# DIGITAL_INPUTS.net
KiCad netlist of a schematic drawn in Altium Designer
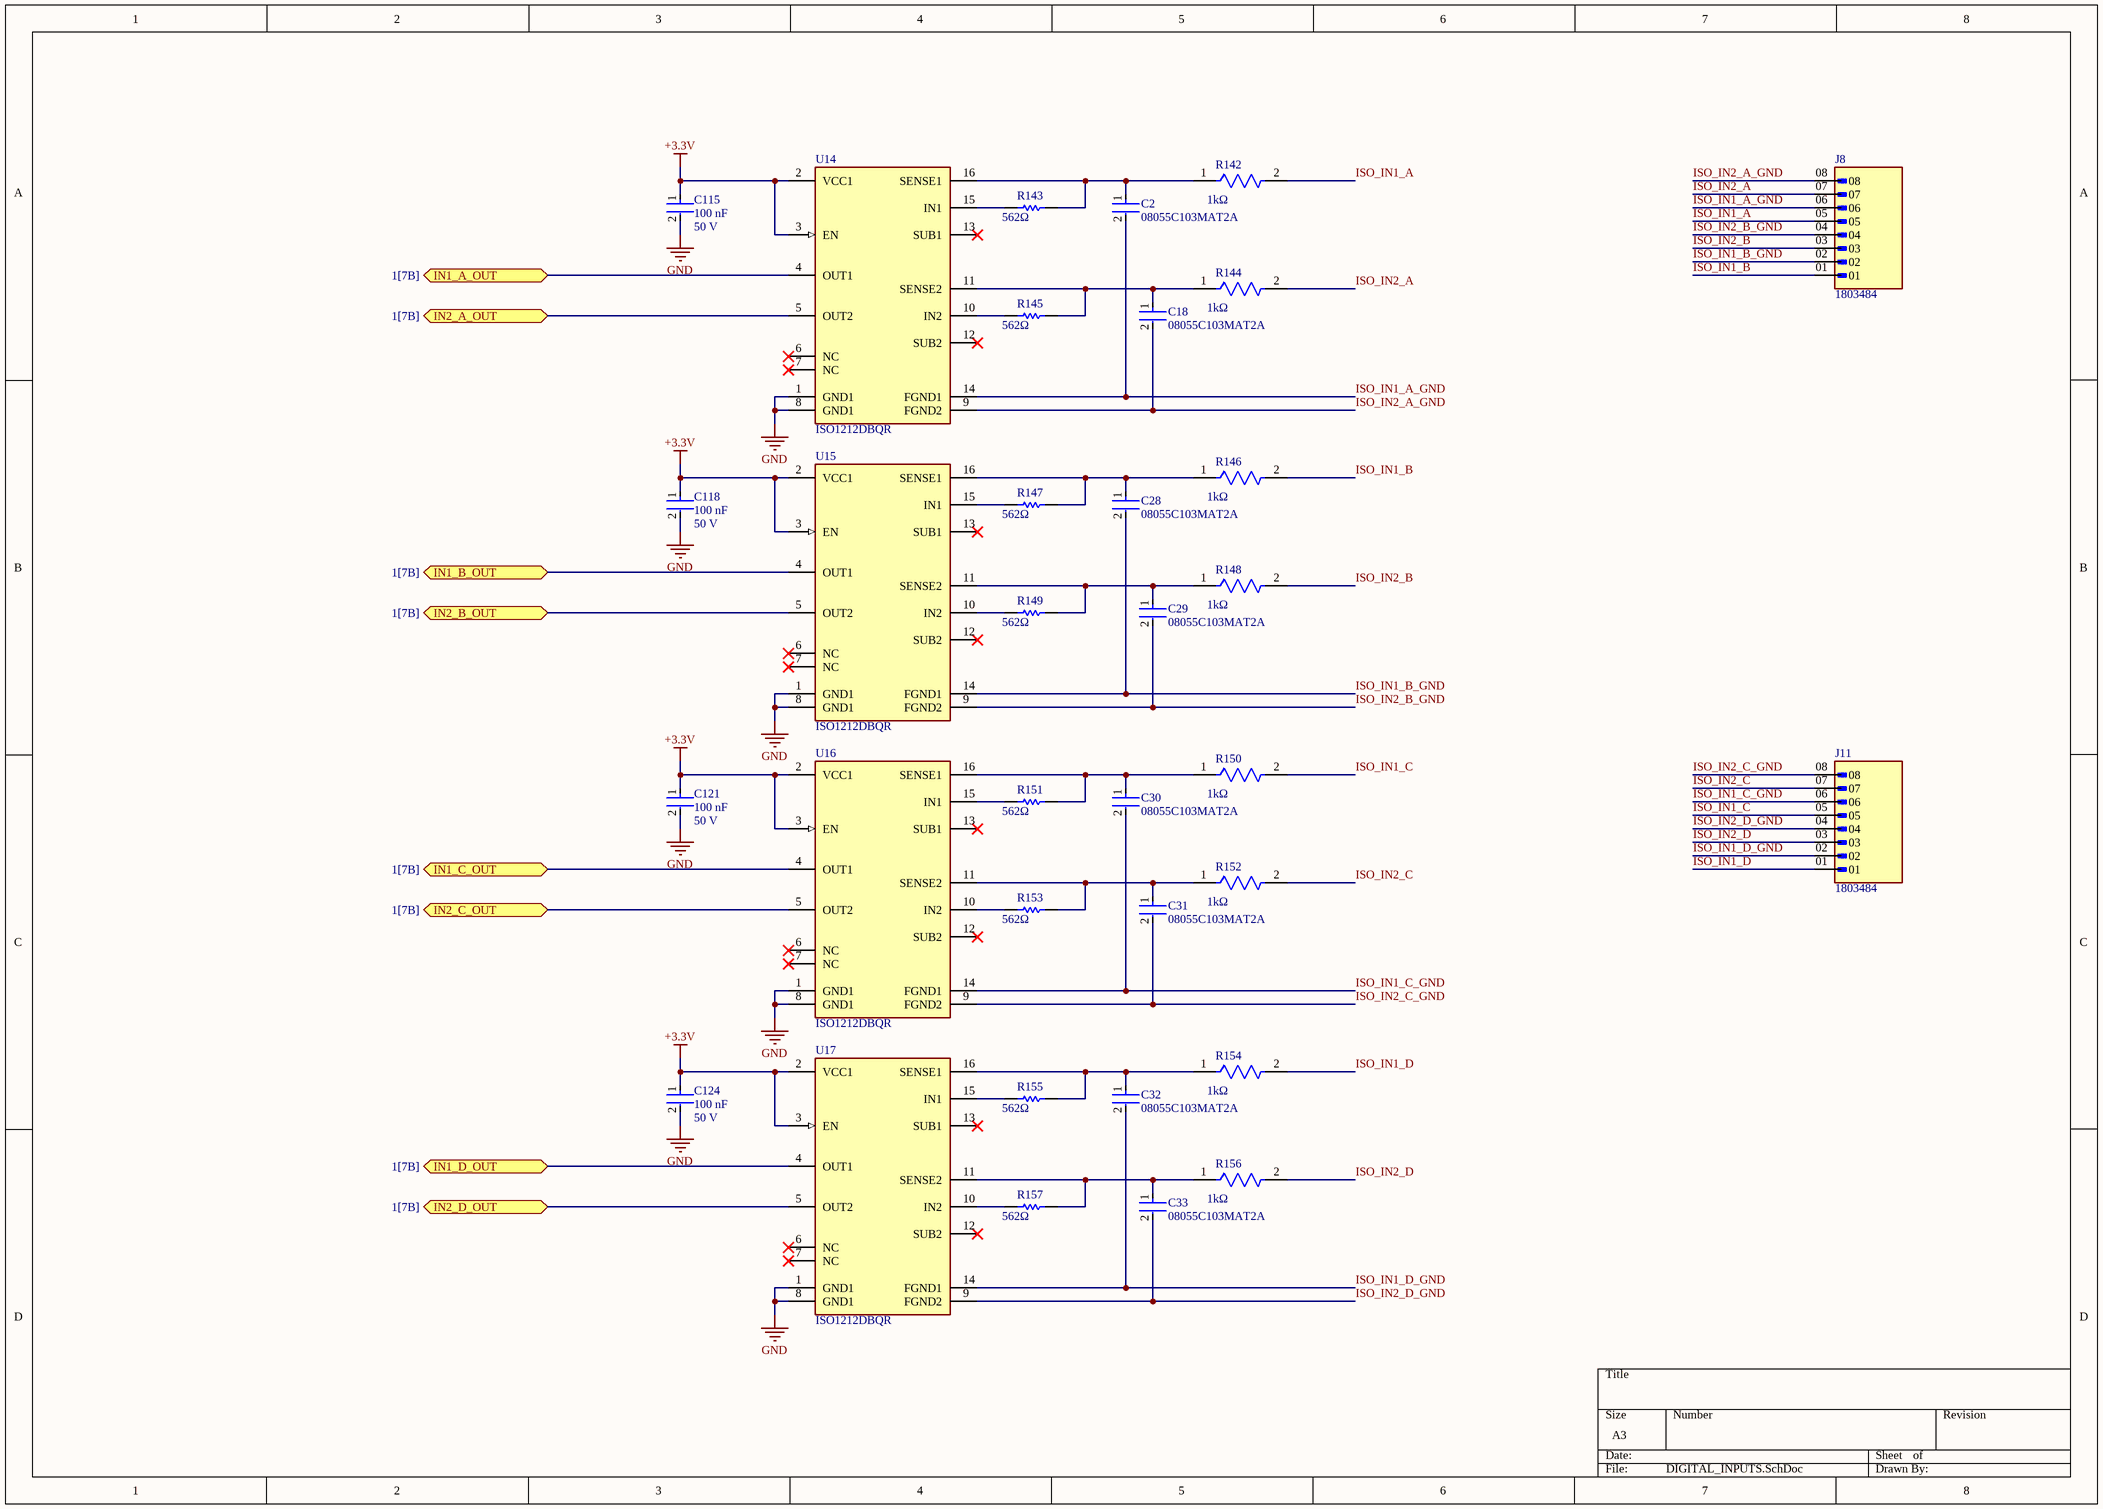
[diagram p0: DIGITAL_INPUTS.SchDoc]

(export (version "E")
  (design (tool "Eeschema 10.0.6"))
  (components
    (comp (ref "C2")
      (value "08055C103MAT2A")
      (footprint "FP-0805-L_2_01_0_2-W_1_25-MFG")
      (description "General Purpose Ceramic Capacitor, 0805, 10nF, 20%, X7R, 0.15, 50V")
      (fields (field (name "VOLTAGE") "50V") (field (name "TOLERANCE") "20%"))
      (libsource (lib "Altium Content Vault") (part "02cd4be3c70576c341d710602a673aa"))
    )
    (comp (ref "C18")
      (value "08055C103MAT2A")
      (footprint "FP-0805-L_2_01_0_2-W_1_25-MFG")
      (description "General Purpose Ceramic Capacitor, 0805, 10nF, 20%, X7R, 0.15, 50V")
      (fields (field (name "VOLTAGE") "50V") (field (name "TOLERANCE") "20%"))
      (libsource (lib "Altium Content Vault") (part "02cd4be3c70576c341d710602a673aa"))
    )
    (comp (ref "C28")
      (value "08055C103MAT2A")
      (footprint "FP-0805-L_2_01_0_2-W_1_25-MFG")
      (description "General Purpose Ceramic Capacitor, 0805, 10nF, 20%, X7R, 0.15, 50V")
      (fields (field (name "VOLTAGE") "50V") (field (name "TOLERANCE") "20%"))
      (libsource (lib "Altium Content Vault") (part "02cd4be3c70576c341d710602a673aa"))
    )
    (comp (ref "C29")
      (value "08055C103MAT2A")
      (footprint "FP-0805-L_2_01_0_2-W_1_25-MFG")
      (description "General Purpose Ceramic Capacitor, 0805, 10nF, 20%, X7R, 0.15, 50V")
      (fields (field (name "VOLTAGE") "50V") (field (name "TOLERANCE") "20%"))
      (libsource (lib "Altium Content Vault") (part "02cd4be3c70576c341d710602a673aa"))
    )
    (comp (ref "C30")
      (value "08055C103MAT2A")
      (footprint "FP-0805-L_2_01_0_2-W_1_25-MFG")
      (description "General Purpose Ceramic Capacitor, 0805, 10nF, 20%, X7R, 0.15, 50V")
      (fields (field (name "VOLTAGE") "50V") (field (name "TOLERANCE") "20%"))
      (libsource (lib "Altium Content Vault") (part "02cd4be3c70576c341d710602a673aa"))
    )
    (comp (ref "C31")
      (value "08055C103MAT2A")
      (footprint "FP-0805-L_2_01_0_2-W_1_25-MFG")
      (description "General Purpose Ceramic Capacitor, 0805, 10nF, 20%, X7R, 0.15, 50V")
      (fields (field (name "VOLTAGE") "50V") (field (name "TOLERANCE") "20%"))
      (libsource (lib "Altium Content Vault") (part "02cd4be3c70576c341d710602a673aa"))
    )
    (comp (ref "C32")
      (value "08055C103MAT2A")
      (footprint "FP-0805-L_2_01_0_2-W_1_25-MFG")
      (description "General Purpose Ceramic Capacitor, 0805, 10nF, 20%, X7R, 0.15, 50V")
      (fields (field (name "VOLTAGE") "50V") (field (name "TOLERANCE") "20%"))
      (libsource (lib "Altium Content Vault") (part "02cd4be3c70576c341d710602a673aa"))
    )
    (comp (ref "C33")
      (value "08055C103MAT2A")
      (footprint "FP-0805-L_2_01_0_2-W_1_25-MFG")
      (description "General Purpose Ceramic Capacitor, 0805, 10nF, 20%, X7R, 0.15, 50V")
      (fields (field (name "VOLTAGE") "50V") (field (name "TOLERANCE") "20%"))
      (libsource (lib "Altium Content Vault") (part "02cd4be3c70576c341d710602a673aa"))
    )
    (comp (ref "C115")
      (value "100 nF")
      (footprint "FP-C0603C-CF-IPC_B")
      (description "CAP CER 0.1UF 50V 20% X7R 0603")
      (fields
        (field (name "VOLTAGE RATING") "50 V")
        (field (name "MANUFACTURER PART NUMBER") "C0603C104M5RACTU")
        (field (name "MANUFACTURER") "KEMET")
      )
      (libsource (lib "Altium Content Vault") (part "b4654b650e69147ec39a6b967a45e02"))
    )
    (comp (ref "C118")
      (value "100 nF")
      (footprint "FP-C0603C-CF-IPC_B")
      (description "CAP CER 0.1UF 50V 20% X7R 0603")
      (fields
        (field (name "VOLTAGE RATING") "50 V")
        (field (name "MANUFACTURER PART NUMBER") "C0603C104M5RACTU")
        (field (name "MANUFACTURER") "KEMET")
      )
      (libsource (lib "Altium Content Vault") (part "b4654b650e69147ec39a6b967a45e02"))
    )
    (comp (ref "C121")
      (value "100 nF")
      (footprint "FP-C0603C-CF-IPC_B")
      (description "CAP CER 0.1UF 50V 20% X7R 0603")
      (fields
        (field (name "VOLTAGE RATING") "50 V")
        (field (name "MANUFACTURER PART NUMBER") "C0603C104M5RACTU")
        (field (name "MANUFACTURER") "KEMET")
      )
      (libsource (lib "Altium Content Vault") (part "b4654b650e69147ec39a6b967a45e02"))
    )
    (comp (ref "C124")
      (value "100 nF")
      (footprint "FP-C0603C-CF-IPC_B")
      (description "CAP CER 0.1UF 50V 20% X7R 0603")
      (fields
        (field (name "VOLTAGE RATING") "50 V")
        (field (name "MANUFACTURER PART NUMBER") "C0603C104M5RACTU")
        (field (name "MANUFACTURER") "KEMET")
      )
      (libsource (lib "Altium Content Vault") (part "b4654b650e69147ec39a6b967a45e02"))
    )
    (comp (ref "J8")
      (value "1803484")
      (footprint "1803484:PHOENIX_1803484")
      (fields (field (name "MF") "{'manufacturer': u'Phoenix Contact'}"))
      (libsource (lib "*") (part "1803484"))
    )
    (comp (ref "J11")
      (value "1803484")
      (footprint "1803484:PHOENIX_1803484")
      (fields (field (name "MF") "{'manufacturer': u'Phoenix Contact'}"))
      (libsource (lib "*") (part "1803484"))
    )
    (comp (ref "R142")
      (value "AC0603FR-071KL")
      (footprint "FP-AC0603-IPC_B")
      (description "RES 1kΩ 1.00% 0.1W 0603")
      (fields (field (name "TOLERANCE") "1%") (field (name "RESISTANCE") "1kΩ"))
      (libsource (lib "Altium Content Vault") (part "1029c3af85768c4190bb7ad29bc67b5"))
    )
    (comp (ref "R143")
      (value "RC0603FR-07562RL")
      (footprint "RESC1608X55X25ML10T15")
      (fields (field (name "MANUFACTURER") "Yageo") (field (name "RESISTANCE") "562Ω"))
      (libsource (lib "Altium Content Vault") (part "RES"))
    )
    (comp (ref "R144")
      (value "AC0603FR-071KL")
      (footprint "FP-AC0603-IPC_B")
      (description "RES 1kΩ 1.00% 0.1W 0603")
      (fields (field (name "TOLERANCE") "1%") (field (name "RESISTANCE") "1kΩ"))
      (libsource (lib "Altium Content Vault") (part "1029c3af85768c4190bb7ad29bc67b5"))
    )
    (comp (ref "R145")
      (value "RC0603FR-07562RL")
      (footprint "RESC1608X55X25ML10T15")
      (fields (field (name "MANUFACTURER") "Yageo") (field (name "RESISTANCE") "562Ω"))
      (libsource (lib "Altium Content Vault") (part "RES"))
    )
    (comp (ref "R146")
      (value "AC0603FR-071KL")
      (footprint "FP-AC0603-IPC_B")
      (description "RES 1kΩ 1.00% 0.1W 0603")
      (fields (field (name "TOLERANCE") "1%") (field (name "RESISTANCE") "1kΩ"))
      (libsource (lib "Altium Content Vault") (part "1029c3af85768c4190bb7ad29bc67b5"))
    )
    (comp (ref "R147")
      (value "RC0603FR-07562RL")
      (footprint "RESC1608X55X25ML10T15")
      (fields (field (name "MANUFACTURER") "Yageo") (field (name "RESISTANCE") "562Ω"))
      (libsource (lib "Altium Content Vault") (part "RES"))
    )
    (comp (ref "R148")
      (value "AC0603FR-071KL")
      (footprint "FP-AC0603-IPC_B")
      (description "RES 1kΩ 1.00% 0.1W 0603")
      (fields (field (name "TOLERANCE") "1%") (field (name "RESISTANCE") "1kΩ"))
      (libsource (lib "Altium Content Vault") (part "1029c3af85768c4190bb7ad29bc67b5"))
    )
    (comp (ref "R149")
      (value "RC0603FR-07562RL")
      (footprint "RESC1608X55X25ML10T15")
      (fields (field (name "MANUFACTURER") "Yageo") (field (name "RESISTANCE") "562Ω"))
      (libsource (lib "Altium Content Vault") (part "RES"))
    )
    (comp (ref "R150")
      (value "AC0603FR-071KL")
      (footprint "FP-AC0603-IPC_B")
      (description "RES 1kΩ 1.00% 0.1W 0603")
      (fields (field (name "TOLERANCE") "1%") (field (name "RESISTANCE") "1kΩ"))
      (libsource (lib "Altium Content Vault") (part "1029c3af85768c4190bb7ad29bc67b5"))
    )
    (comp (ref "R151")
      (value "RC0603FR-07562RL")
      (footprint "RESC1608X55X25ML10T15")
      (fields (field (name "MANUFACTURER") "Yageo") (field (name "RESISTANCE") "562Ω"))
      (libsource (lib "Altium Content Vault") (part "RES"))
    )
    (comp (ref "R152")
      (value "AC0603FR-071KL")
      (footprint "FP-AC0603-IPC_B")
      (description "RES 1kΩ 1.00% 0.1W 0603")
      (fields (field (name "TOLERANCE") "1%") (field (name "RESISTANCE") "1kΩ"))
      (libsource (lib "Altium Content Vault") (part "1029c3af85768c4190bb7ad29bc67b5"))
    )
    (comp (ref "R153")
      (value "RC0603FR-07562RL")
      (footprint "RESC1608X55X25ML10T15")
      (fields (field (name "MANUFACTURER") "Yageo") (field (name "RESISTANCE") "562Ω"))
      (libsource (lib "Altium Content Vault") (part "RES"))
    )
    (comp (ref "R154")
      (value "AC0603FR-071KL")
      (footprint "FP-AC0603-IPC_B")
      (description "RES 1kΩ 1.00% 0.1W 0603")
      (fields (field (name "TOLERANCE") "1%") (field (name "RESISTANCE") "1kΩ"))
      (libsource (lib "Altium Content Vault") (part "1029c3af85768c4190bb7ad29bc67b5"))
    )
    (comp (ref "R155")
      (value "RC0603FR-07562RL")
      (footprint "RESC1608X55X25ML10T15")
      (fields (field (name "MANUFACTURER") "Yageo") (field (name "RESISTANCE") "562Ω"))
      (libsource (lib "Altium Content Vault") (part "RES"))
    )
    (comp (ref "R156")
      (value "AC0603FR-071KL")
      (footprint "FP-AC0603-IPC_B")
      (description "RES 1kΩ 1.00% 0.1W 0603")
      (fields (field (name "TOLERANCE") "1%") (field (name "RESISTANCE") "1kΩ"))
      (libsource (lib "Altium Content Vault") (part "1029c3af85768c4190bb7ad29bc67b5"))
    )
    (comp (ref "R157")
      (value "RC0603FR-07562RL")
      (footprint "RESC1608X55X25ML10T15")
      (fields (field (name "MANUFACTURER") "Yageo") (field (name "RESISTANCE") "562Ω"))
      (libsource (lib "Altium Content Vault") (part "RES"))
    )
    (comp (ref "U14")
      (value "ISO1212DBQR")
      (footprint "FP-DBQ0016A-MFG")
      (description "ISOLATED 24-V TO 60-V DIGITAL IN")
      (fields
        (field (name "OCTOPART") "https://octopart.com/iso1212dbqr-texas+instruments-84619664")
        (field (name "MANUFACTURER") "Texas Instruments")
      )
      (libsource (lib "Altium Content Vault") (part "047d738653624c8e0ece078ac6d36bd"))
    )
    (comp (ref "U15")
      (value "ISO1212DBQR")
      (footprint "FP-DBQ0016A-MFG")
      (description "ISOLATED 24-V TO 60-V DIGITAL IN")
      (fields
        (field (name "OCTOPART") "https://octopart.com/iso1212dbqr-texas+instruments-84619664")
        (field (name "MANUFACTURER") "Texas Instruments")
      )
      (libsource (lib "Altium Content Vault") (part "047d738653624c8e0ece078ac6d36bd"))
    )
    (comp (ref "U16")
      (value "ISO1212DBQR")
      (footprint "FP-DBQ0016A-MFG")
      (description "ISOLATED 24-V TO 60-V DIGITAL IN")
      (fields
        (field (name "OCTOPART") "https://octopart.com/iso1212dbqr-texas+instruments-84619664")
        (field (name "MANUFACTURER") "Texas Instruments")
      )
      (libsource (lib "Altium Content Vault") (part "047d738653624c8e0ece078ac6d36bd"))
    )
    (comp (ref "U17")
      (value "ISO1212DBQR")
      (footprint "FP-DBQ0016A-MFG")
      (description "ISOLATED 24-V TO 60-V DIGITAL IN")
      (fields
        (field (name "OCTOPART") "https://octopart.com/iso1212dbqr-texas+instruments-84619664")
        (field (name "MANUFACTURER") "Texas Instruments")
      )
      (libsource (lib "Altium Content Vault") (part "047d738653624c8e0ece078ac6d36bd"))
    )
  )
  (nets
    (net (code "1") (name "+3.3V") (class "Default")
      (node (ref "C115") (pin "1") (pinfunction "1_1") (pintype "passive"))
      (node (ref "C118") (pin "1") (pinfunction "1_1") (pintype "passive"))
      (node (ref "C121") (pin "1") (pinfunction "1_1") (pintype "passive"))
      (node (ref "C124") (pin "1") (pinfunction "1_1") (pintype "passive"))
      (node (ref "U14") (pin "2") (pinfunction "VCC1_2") (pintype "power_in"))
      (node (ref "U14") (pin "3") (pinfunction "EN_3") (pintype "input"))
      (node (ref "U15") (pin "2") (pinfunction "VCC1_2") (pintype "power_in"))
      (node (ref "U15") (pin "3") (pinfunction "EN_3") (pintype "input"))
      (node (ref "U16") (pin "2") (pinfunction "VCC1_2") (pintype "power_in"))
      (node (ref "U16") (pin "3") (pinfunction "EN_3") (pintype "input"))
      (node (ref "U17") (pin "2") (pinfunction "VCC1_2") (pintype "power_in"))
      (node (ref "U17") (pin "3") (pinfunction "EN_3") (pintype "input"))
    )
    (net (code "2") (name "/IN1_A_OUT") (class "Default")
      (node (ref "U14") (pin "4") (pinfunction "OUT1_4") (pintype "passive"))
    )
    (net (code "3") (name "/IN1_B_OUT") (class "Default")
      (node (ref "U15") (pin "4") (pinfunction "OUT1_4") (pintype "passive"))
    )
    (net (code "4") (name "/IN1_C_OUT") (class "Default")
      (node (ref "U16") (pin "4") (pinfunction "OUT1_4") (pintype "passive"))
    )
    (net (code "5") (name "/IN1_D_OUT") (class "Default")
      (node (ref "U17") (pin "4") (pinfunction "OUT1_4") (pintype "passive"))
    )
    (net (code "6") (name "/IN2_A_OUT") (class "Default")
      (node (ref "U14") (pin "5") (pinfunction "OUT2_5") (pintype "passive"))
    )
    (net (code "7") (name "/IN2_B_OUT") (class "Default")
      (node (ref "U15") (pin "5") (pinfunction "OUT2_5") (pintype "passive"))
    )
    (net (code "8") (name "/IN2_C_OUT") (class "Default")
      (node (ref "U16") (pin "5") (pinfunction "OUT2_5") (pintype "passive"))
    )
    (net (code "9") (name "/IN2_D_OUT") (class "Default")
      (node (ref "U17") (pin "5") (pinfunction "OUT2_5") (pintype "passive"))
    )
    (net (code "10") (name "/ISO_IN1_A") (class "Default")
      (node (ref "J8") (pin "05") (pinfunction "05_05") (pintype "passive"))
      (node (ref "R142") (pin "2") (pinfunction "2_2") (pintype "passive"))
    )
    (net (code "11") (name "/ISO_IN1_A_GND") (class "Default")
      (node (ref "C2") (pin "2") (pinfunction "2_2") (pintype "passive"))
      (node (ref "J8") (pin "06") (pinfunction "06_06") (pintype "passive"))
      (node (ref "U14") (pin "14") (pinfunction "FGND1_14") (pintype "power_in"))
    )
    (net (code "12") (name "/ISO_IN1_B") (class "Default")
      (node (ref "J8") (pin "01") (pinfunction "01_01") (pintype "passive"))
      (node (ref "R146") (pin "2") (pinfunction "2_2") (pintype "passive"))
    )
    (net (code "13") (name "/ISO_IN1_B_GND") (class "Default")
      (node (ref "C28") (pin "2") (pinfunction "2_2") (pintype "passive"))
      (node (ref "J8") (pin "02") (pinfunction "02_02") (pintype "passive"))
      (node (ref "U15") (pin "14") (pinfunction "FGND1_14") (pintype "power_in"))
    )
    (net (code "14") (name "/ISO_IN1_C") (class "Default")
      (node (ref "J11") (pin "05") (pinfunction "05_05") (pintype "passive"))
      (node (ref "R150") (pin "2") (pinfunction "2_2") (pintype "passive"))
    )
    (net (code "15") (name "/ISO_IN1_C_GND") (class "Default")
      (node (ref "C30") (pin "2") (pinfunction "2_2") (pintype "passive"))
      (node (ref "J11") (pin "06") (pinfunction "06_06") (pintype "passive"))
      (node (ref "U16") (pin "14") (pinfunction "FGND1_14") (pintype "power_in"))
    )
    (net (code "16") (name "/ISO_IN1_D") (class "Default")
      (node (ref "J11") (pin "01") (pinfunction "01_01") (pintype "passive"))
      (node (ref "R154") (pin "2") (pinfunction "2_2") (pintype "passive"))
    )
    (net (code "17") (name "/ISO_IN1_D_GND") (class "Default")
      (node (ref "C32") (pin "2") (pinfunction "2_2") (pintype "passive"))
      (node (ref "J11") (pin "02") (pinfunction "02_02") (pintype "passive"))
      (node (ref "U17") (pin "14") (pinfunction "FGND1_14") (pintype "power_in"))
    )
    (net (code "18") (name "/ISO_IN2_A") (class "Default")
      (node (ref "J8") (pin "07") (pinfunction "07_07") (pintype "passive"))
      (node (ref "R144") (pin "2") (pinfunction "2_2") (pintype "passive"))
    )
    (net (code "19") (name "/ISO_IN2_A_GND") (class "Default")
      (node (ref "C18") (pin "2") (pinfunction "2_2") (pintype "passive"))
      (node (ref "J8") (pin "08") (pinfunction "08_08") (pintype "passive"))
      (node (ref "U14") (pin "9") (pinfunction "FGND2_9") (pintype "power_in"))
    )
    (net (code "20") (name "/ISO_IN2_B") (class "Default")
      (node (ref "J8") (pin "03") (pinfunction "03_03") (pintype "passive"))
      (node (ref "R148") (pin "2") (pinfunction "2_2") (pintype "passive"))
    )
    (net (code "21") (name "/ISO_IN2_B_GND") (class "Default")
      (node (ref "C29") (pin "2") (pinfunction "2_2") (pintype "passive"))
      (node (ref "J8") (pin "04") (pinfunction "04_04") (pintype "passive"))
      (node (ref "U15") (pin "9") (pinfunction "FGND2_9") (pintype "power_in"))
    )
    (net (code "22") (name "/ISO_IN2_C") (class "Default")
      (node (ref "J11") (pin "07") (pinfunction "07_07") (pintype "passive"))
      (node (ref "R152") (pin "2") (pinfunction "2_2") (pintype "passive"))
    )
    (net (code "23") (name "/ISO_IN2_C_GND") (class "Default")
      (node (ref "C31") (pin "2") (pinfunction "2_2") (pintype "passive"))
      (node (ref "J11") (pin "08") (pinfunction "08_08") (pintype "passive"))
      (node (ref "U16") (pin "9") (pinfunction "FGND2_9") (pintype "power_in"))
    )
    (net (code "24") (name "/ISO_IN2_D") (class "Default")
      (node (ref "J11") (pin "03") (pinfunction "03_03") (pintype "passive"))
      (node (ref "R156") (pin "2") (pinfunction "2_2") (pintype "passive"))
    )
    (net (code "25") (name "/ISO_IN2_D_GND") (class "Default")
      (node (ref "C33") (pin "2") (pinfunction "2_2") (pintype "passive"))
      (node (ref "J11") (pin "04") (pinfunction "04_04") (pintype "passive"))
      (node (ref "U17") (pin "9") (pinfunction "FGND2_9") (pintype "power_in"))
    )
    (net (code "26") (name "GND") (class "Default")
      (node (ref "C115") (pin "2") (pinfunction "2_2") (pintype "passive"))
      (node (ref "C118") (pin "2") (pinfunction "2_2") (pintype "passive"))
      (node (ref "C121") (pin "2") (pinfunction "2_2") (pintype "passive"))
      (node (ref "C124") (pin "2") (pinfunction "2_2") (pintype "passive"))
      (node (ref "U14") (pin "1") (pinfunction "GND1_1") (pintype "power_in"))
      (node (ref "U14") (pin "8") (pinfunction "GND1_8") (pintype "power_in"))
      (node (ref "U15") (pin "1") (pinfunction "GND1_1") (pintype "power_in"))
      (node (ref "U15") (pin "8") (pinfunction "GND1_8") (pintype "power_in"))
      (node (ref "U16") (pin "1") (pinfunction "GND1_1") (pintype "power_in"))
      (node (ref "U16") (pin "8") (pinfunction "GND1_8") (pintype "power_in"))
      (node (ref "U17") (pin "1") (pinfunction "GND1_1") (pintype "power_in"))
      (node (ref "U17") (pin "8") (pinfunction "GND1_8") (pintype "power_in"))
    )
    (net (code "27") (name "Net-(U14-IN1)") (class "Default")
      (node (ref "R143") (pin "1") (pinfunction "1_1") (pintype "passive"))
      (node (ref "U14") (pin "15") (pinfunction "IN1_15") (pintype "passive"))
    )
    (net (code "28") (name "Net-(U14-IN2)") (class "Default")
      (node (ref "R145") (pin "1") (pinfunction "1_1") (pintype "passive"))
      (node (ref "U14") (pin "10") (pinfunction "IN2_10") (pintype "passive"))
    )
    (net (code "29") (name "Net-(U14-SENSE1)") (class "Default")
      (node (ref "C2") (pin "1") (pinfunction "1_1") (pintype "passive"))
      (node (ref "R142") (pin "1") (pinfunction "1_1") (pintype "passive"))
      (node (ref "R143") (pin "2") (pinfunction "2_2") (pintype "passive"))
      (node (ref "U14") (pin "16") (pinfunction "SENSE1_16") (pintype "passive"))
    )
    (net (code "30") (name "Net-(U14-SENSE2)") (class "Default")
      (node (ref "C18") (pin "1") (pinfunction "1_1") (pintype "passive"))
      (node (ref "R144") (pin "1") (pinfunction "1_1") (pintype "passive"))
      (node (ref "R145") (pin "2") (pinfunction "2_2") (pintype "passive"))
      (node (ref "U14") (pin "11") (pinfunction "SENSE2_11") (pintype "passive"))
    )
    (net (code "31") (name "Net-(U15-IN1)") (class "Default")
      (node (ref "R147") (pin "1") (pinfunction "1_1") (pintype "passive"))
      (node (ref "U15") (pin "15") (pinfunction "IN1_15") (pintype "passive"))
    )
    (net (code "32") (name "Net-(U15-IN2)") (class "Default")
      (node (ref "R149") (pin "1") (pinfunction "1_1") (pintype "passive"))
      (node (ref "U15") (pin "10") (pinfunction "IN2_10") (pintype "passive"))
    )
    (net (code "33") (name "Net-(U15-SENSE1)") (class "Default")
      (node (ref "C28") (pin "1") (pinfunction "1_1") (pintype "passive"))
      (node (ref "R146") (pin "1") (pinfunction "1_1") (pintype "passive"))
      (node (ref "R147") (pin "2") (pinfunction "2_2") (pintype "passive"))
      (node (ref "U15") (pin "16") (pinfunction "SENSE1_16") (pintype "passive"))
    )
    (net (code "34") (name "Net-(U15-SENSE2)") (class "Default")
      (node (ref "C29") (pin "1") (pinfunction "1_1") (pintype "passive"))
      (node (ref "R148") (pin "1") (pinfunction "1_1") (pintype "passive"))
      (node (ref "R149") (pin "2") (pinfunction "2_2") (pintype "passive"))
      (node (ref "U15") (pin "11") (pinfunction "SENSE2_11") (pintype "passive"))
    )
    (net (code "35") (name "Net-(U16-IN1)") (class "Default")
      (node (ref "R151") (pin "1") (pinfunction "1_1") (pintype "passive"))
      (node (ref "U16") (pin "15") (pinfunction "IN1_15") (pintype "passive"))
    )
    (net (code "36") (name "Net-(U16-IN2)") (class "Default")
      (node (ref "R153") (pin "1") (pinfunction "1_1") (pintype "passive"))
      (node (ref "U16") (pin "10") (pinfunction "IN2_10") (pintype "passive"))
    )
    (net (code "37") (name "Net-(U16-SENSE1)") (class "Default")
      (node (ref "C30") (pin "1") (pinfunction "1_1") (pintype "passive"))
      (node (ref "R150") (pin "1") (pinfunction "1_1") (pintype "passive"))
      (node (ref "R151") (pin "2") (pinfunction "2_2") (pintype "passive"))
      (node (ref "U16") (pin "16") (pinfunction "SENSE1_16") (pintype "passive"))
    )
    (net (code "38") (name "Net-(U16-SENSE2)") (class "Default")
      (node (ref "C31") (pin "1") (pinfunction "1_1") (pintype "passive"))
      (node (ref "R152") (pin "1") (pinfunction "1_1") (pintype "passive"))
      (node (ref "R153") (pin "2") (pinfunction "2_2") (pintype "passive"))
      (node (ref "U16") (pin "11") (pinfunction "SENSE2_11") (pintype "passive"))
    )
    (net (code "39") (name "Net-(U17-IN1)") (class "Default")
      (node (ref "R155") (pin "1") (pinfunction "1_1") (pintype "passive"))
      (node (ref "U17") (pin "15") (pinfunction "IN1_15") (pintype "passive"))
    )
    (net (code "40") (name "Net-(U17-IN2)") (class "Default")
      (node (ref "R157") (pin "1") (pinfunction "1_1") (pintype "passive"))
      (node (ref "U17") (pin "10") (pinfunction "IN2_10") (pintype "passive"))
    )
    (net (code "41") (name "Net-(U17-SENSE1)") (class "Default")
      (node (ref "C32") (pin "1") (pinfunction "1_1") (pintype "passive"))
      (node (ref "R154") (pin "1") (pinfunction "1_1") (pintype "passive"))
      (node (ref "R155") (pin "2") (pinfunction "2_2") (pintype "passive"))
      (node (ref "U17") (pin "16") (pinfunction "SENSE1_16") (pintype "passive"))
    )
    (net (code "42") (name "Net-(U17-SENSE2)") (class "Default")
      (node (ref "C33") (pin "1") (pinfunction "1_1") (pintype "passive"))
      (node (ref "R156") (pin "1") (pinfunction "1_1") (pintype "passive"))
      (node (ref "R157") (pin "2") (pinfunction "2_2") (pintype "passive"))
      (node (ref "U17") (pin "11") (pinfunction "SENSE2_11") (pintype "passive"))
    )
    (net (code "43") (name "unconnected-(U14-NC-Pad6)") (class "Default")
      (node (ref "U14") (pin "6") (pinfunction "NC_6") (pintype "passive+no_connect"))
    )
    (net (code "44") (name "unconnected-(U14-NC-Pad7)") (class "Default")
      (node (ref "U14") (pin "7") (pinfunction "NC_7") (pintype "passive+no_connect"))
    )
    (net (code "45") (name "unconnected-(U14-SUB1-Pad13)") (class "Default")
      (node (ref "U14") (pin "13") (pinfunction "SUB1_13") (pintype "passive+no_connect"))
    )
    (net (code "46") (name "unconnected-(U14-SUB2-Pad12)") (class "Default")
      (node (ref "U14") (pin "12") (pinfunction "SUB2_12") (pintype "passive+no_connect"))
    )
    (net (code "47") (name "unconnected-(U15-NC-Pad6)") (class "Default")
      (node (ref "U15") (pin "6") (pinfunction "NC_6") (pintype "passive+no_connect"))
    )
    (net (code "48") (name "unconnected-(U15-NC-Pad7)") (class "Default")
      (node (ref "U15") (pin "7") (pinfunction "NC_7") (pintype "passive+no_connect"))
    )
    (net (code "49") (name "unconnected-(U15-SUB1-Pad13)") (class "Default")
      (node (ref "U15") (pin "13") (pinfunction "SUB1_13") (pintype "passive+no_connect"))
    )
    (net (code "50") (name "unconnected-(U15-SUB2-Pad12)") (class "Default")
      (node (ref "U15") (pin "12") (pinfunction "SUB2_12") (pintype "passive+no_connect"))
    )
    (net (code "51") (name "unconnected-(U16-NC-Pad6)") (class "Default")
      (node (ref "U16") (pin "6") (pinfunction "NC_6") (pintype "passive+no_connect"))
    )
    (net (code "52") (name "unconnected-(U16-NC-Pad7)") (class "Default")
      (node (ref "U16") (pin "7") (pinfunction "NC_7") (pintype "passive+no_connect"))
    )
    (net (code "53") (name "unconnected-(U16-SUB1-Pad13)") (class "Default")
      (node (ref "U16") (pin "13") (pinfunction "SUB1_13") (pintype "passive+no_connect"))
    )
    (net (code "54") (name "unconnected-(U16-SUB2-Pad12)") (class "Default")
      (node (ref "U16") (pin "12") (pinfunction "SUB2_12") (pintype "passive+no_connect"))
    )
    (net (code "55") (name "unconnected-(U17-NC-Pad6)") (class "Default")
      (node (ref "U17") (pin "6") (pinfunction "NC_6") (pintype "passive+no_connect"))
    )
    (net (code "56") (name "unconnected-(U17-NC-Pad7)") (class "Default")
      (node (ref "U17") (pin "7") (pinfunction "NC_7") (pintype "passive+no_connect"))
    )
    (net (code "57") (name "unconnected-(U17-SUB1-Pad13)") (class "Default")
      (node (ref "U17") (pin "13") (pinfunction "SUB1_13") (pintype "passive+no_connect"))
    )
    (net (code "58") (name "unconnected-(U17-SUB2-Pad12)") (class "Default")
      (node (ref "U17") (pin "12") (pinfunction "SUB2_12") (pintype "passive+no_connect"))
    )
  )
)
